# UBW32_MX460_v262.net
KiCad netlist of a schematic drawn in EAGLE
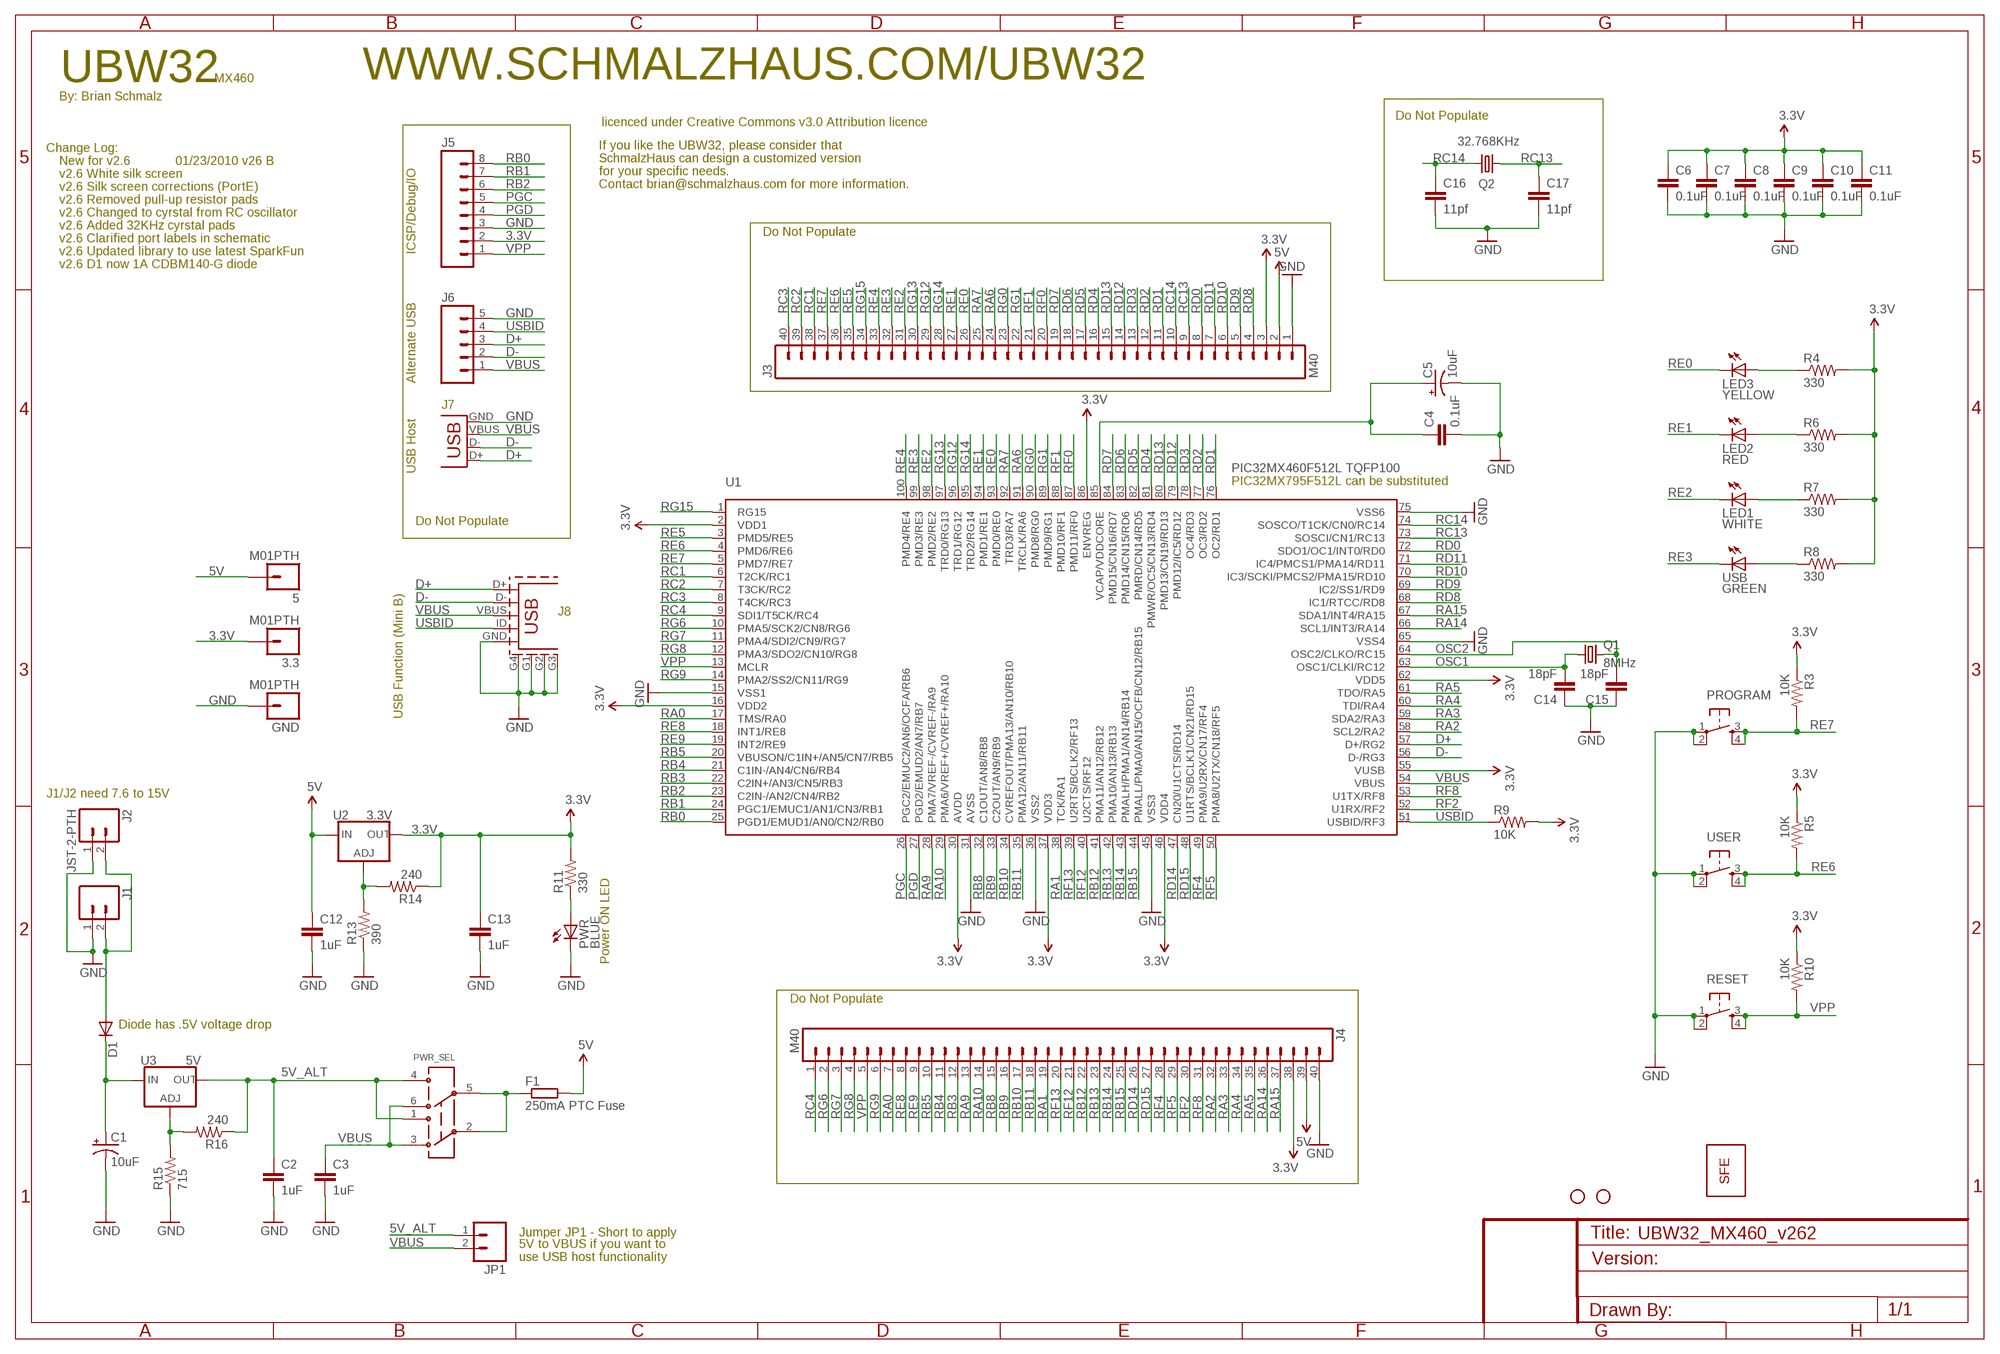
[diagram p0: schematic, sheet 1]

(export (version "E")
  (design (tool "Eeschema 10.0.6"))
  (components
    (comp (ref "3.3")
      (value "M01PTH")
      (footprint "eagle-import:1X01")
      (libsource (lib "eagle-import") (part "M01PTH"))
    )
    (comp (ref "5")
      (value "M01PTH")
      (footprint "eagle-import:1X01")
      (libsource (lib "eagle-import") (part "M01PTH"))
    )
    (comp (ref "C1")
      (value "10uF")
      (footprint "eagle-import:EIA3528")
      (libsource (lib "eagle-import") (part "CAP_POL3528"))
    )
    (comp (ref "C2")
      (value "1uF")
      (footprint "eagle-import:0402-CAP")
      (libsource (lib "eagle-import") (part "CAP0402-CAP"))
    )
    (comp (ref "C3")
      (value "1uF")
      (footprint "eagle-import:0402-CAP")
      (libsource (lib "eagle-import") (part "CAP0402-CAP"))
    )
    (comp (ref "C4")
      (value "0.1uF")
      (footprint "eagle-import:0402-CAP")
      (libsource (lib "eagle-import") (part "CAP0402-CAP"))
    )
    (comp (ref "C5")
      (value "10uF")
      (footprint "eagle-import:EIA3528")
      (libsource (lib "eagle-import") (part "CAP_POL3528"))
    )
    (comp (ref "C6")
      (value "0.1uF")
      (footprint "eagle-import:0402-CAP")
      (libsource (lib "eagle-import") (part "CAP0402-CAP"))
    )
    (comp (ref "C7")
      (value "0.1uF")
      (footprint "eagle-import:0402-CAP")
      (libsource (lib "eagle-import") (part "CAP0402-CAP"))
    )
    (comp (ref "C8")
      (value "0.1uF")
      (footprint "eagle-import:0402-CAP")
      (libsource (lib "eagle-import") (part "CAP0402-CAP"))
    )
    (comp (ref "C9")
      (value "0.1uF")
      (footprint "eagle-import:0402-CAP")
      (libsource (lib "eagle-import") (part "CAP0402-CAP"))
    )
    (comp (ref "C10")
      (value "0.1uF")
      (footprint "eagle-import:C0402")
      (libsource (lib "eagle-import") (part "CAP0402"))
    )
    (comp (ref "C11")
      (value "0.1uF")
      (footprint "eagle-import:0402-CAP")
      (libsource (lib "eagle-import") (part "CAP0402-CAP"))
    )
    (comp (ref "C12")
      (value "1uF")
      (footprint "eagle-import:C0402")
      (libsource (lib "eagle-import") (part "CAP0402"))
    )
    (comp (ref "C13")
      (value "1uF")
      (footprint "eagle-import:C0402")
      (libsource (lib "eagle-import") (part "CAP0402"))
    )
    (comp (ref "C14")
      (value "18pF")
      (footprint "eagle-import:0402-CAP")
      (libsource (lib "eagle-import") (part "CAP0402-CAP"))
    )
    (comp (ref "C15")
      (value "18pF")
      (footprint "eagle-import:0402-CAP")
      (libsource (lib "eagle-import") (part "CAP0402-CAP"))
    )
    (comp (ref "C16")
      (value "11pf")
      (footprint "eagle-import:0402-CAP")
      (libsource (lib "eagle-import") (part "CAP0402-CAP"))
    )
    (comp (ref "C17")
      (value "11pf")
      (footprint "eagle-import:0402-CAP")
      (libsource (lib "eagle-import") (part "CAP0402-CAP"))
    )
    (comp (ref "D1")
      (value "DIODESMA")
      (footprint "eagle-import:SMA-DIODE")
      (libsource (lib "eagle-import") (part "DIODESMA"))
    )
    (comp (ref "F1")
      (value "250mA PTC Fuse")
      (footprint "eagle-import:R1206")
      (libsource (lib "eagle-import") (part "R-EU_R1206"))
    )
    (comp (ref "GND")
      (value "M01PTH")
      (footprint "eagle-import:1X01")
      (libsource (lib "eagle-import") (part "M01PTH"))
    )
    (comp (ref "J1")
      (value "M02PTH")
      (footprint "eagle-import:1X02")
      (libsource (lib "eagle-import") (part "SparkFun-12-01-09_M02PTH"))
    )
    (comp (ref "J2")
      (value "JST-2-PTH")
      (footprint "eagle-import:S2B-PH")
      (libsource (lib "eagle-import") (part "M02-JST-2MM-SMT"))
    )
    (comp (ref "J3")
      (value "M40")
      (footprint "eagle-import:1X40")
      (libsource (lib "eagle-import") (part "M40"))
    )
    (comp (ref "J4")
      (value "M40")
      (footprint "eagle-import:1X40")
      (libsource (lib "eagle-import") (part "M40"))
    )
    (comp (ref "J5")
      (value "M08")
      (footprint "eagle-import:1X08")
      (libsource (lib "eagle-import") (part "M08"))
    )
    (comp (ref "J6")
      (value "M05PTH")
      (footprint "eagle-import:1X05")
      (libsource (lib "eagle-import") (part "M05PTH"))
    )
    (comp (ref "J7")
      (value "USB-A-S")
      (footprint "eagle-import:USB-A-S")
      (libsource (lib "eagle-import") (part "USB-A-S"))
    )
    (comp (ref "J8")
      (value "USB-MINIB")
      (footprint "eagle-import:USB-MINIB")
      (libsource (lib "eagle-import") (part "USB_5PIN"))
    )
    (comp (ref "JP1")
      (value "M02PTH")
      (footprint "eagle-import:1X02")
      (libsource (lib "eagle-import") (part "SparkFun-12-01-09_M02PTH"))
    )
    (comp (ref "LED1")
      (value "WHITE")
      (footprint "eagle-import:LED-0603")
      (libsource (lib "eagle-import") (part "LED0603"))
    )
    (comp (ref "LED2")
      (value "RED")
      (footprint "eagle-import:LED-0603")
      (libsource (lib "eagle-import") (part "LED0603"))
    )
    (comp (ref "LED3")
      (value "YELLOW")
      (footprint "eagle-import:LED-0603")
      (libsource (lib "eagle-import") (part "LED0603"))
    )
    (comp (ref "PROGRAM")
      (value "TAC_SWITCHSND")
      (footprint "eagle-import:TACTILE_SWITCH_SMD")
      (libsource (lib "eagle-import") (part "TAC_SWITCHSND"))
    )
    (comp (ref "PWR")
      (value "BLUE")
      (footprint "eagle-import:LED-0603")
      (libsource (lib "eagle-import") (part "LED0603"))
    )
    (comp (ref "PWR_SEL")
      (value "AYZ0202")
      (footprint "eagle-import:AYZ0202")
      (libsource (lib "eagle-import") (part "AYZ0202"))
    )
    (comp (ref "Q1")
      (value "8MHz")
      (footprint "eagle-import:CRYSTAL-SMD-5X3")
      (libsource (lib "eagle-import") (part "SparkFun11_03_09_CRYSTAL5X3"))
    )
    (comp (ref "Q2")
      (value "32.768KHz")
      (footprint "eagle-import:CRYSTAL-32KHZ-SMD")
      (libsource (lib "eagle-import") (part "CRYSTAL32-SMD"))
    )
    (comp (ref "R3")
      (value "10K")
      (footprint "eagle-import:0402-RES")
      (libsource (lib "eagle-import") (part "RESISTOR0402-RES"))
    )
    (comp (ref "R4")
      (value "330")
      (footprint "eagle-import:0402-RES")
      (libsource (lib "eagle-import") (part "RESISTOR0402-RES"))
    )
    (comp (ref "R5")
      (value "10K")
      (footprint "eagle-import:0402-RES")
      (libsource (lib "eagle-import") (part "RESISTOR0402-RES"))
    )
    (comp (ref "R6")
      (value "330")
      (footprint "eagle-import:0402-RES")
      (libsource (lib "eagle-import") (part "RESISTOR0402-RES"))
    )
    (comp (ref "R7")
      (value "330")
      (footprint "eagle-import:0402-RES")
      (libsource (lib "eagle-import") (part "RESISTOR0402-RES"))
    )
    (comp (ref "R8")
      (value "330")
      (footprint "eagle-import:0402-RES")
      (libsource (lib "eagle-import") (part "RESISTOR0402-RES"))
    )
    (comp (ref "R9")
      (value "10K")
      (footprint "eagle-import:0402-RES")
      (libsource (lib "eagle-import") (part "RESISTOR0402-RES"))
    )
    (comp (ref "R10")
      (value "10K")
      (footprint "eagle-import:0402-RES")
      (libsource (lib "eagle-import") (part "RESISTOR0402-RES"))
    )
    (comp (ref "R11")
      (value "330")
      (footprint "eagle-import:0402-RES")
      (libsource (lib "eagle-import") (part "RESISTOR0402-RES"))
    )
    (comp (ref "R13")
      (value "390")
      (footprint "eagle-import:0402-RES")
      (libsource (lib "eagle-import") (part "RESISTOR0402-RES"))
    )
    (comp (ref "R14")
      (value "240")
      (footprint "eagle-import:0402-RES")
      (libsource (lib "eagle-import") (part "RESISTOR0402-RES"))
    )
    (comp (ref "R15")
      (value "715")
      (footprint "eagle-import:0402-RES")
      (libsource (lib "eagle-import") (part "RESISTOR0402-RES"))
    )
    (comp (ref "R16")
      (value "240")
      (footprint "eagle-import:0402-RES")
      (libsource (lib "eagle-import") (part "RESISTOR0402-RES"))
    )
    (comp (ref "RESET")
      (value "TAC_SWITCHSND")
      (footprint "eagle-import:TACTILE_SWITCH_SMD")
      (libsource (lib "eagle-import") (part "TAC_SWITCHSND"))
    )
    (comp (ref "U$4")
      (value "LOGO-SFENEW")
      (footprint "eagle-import:SFE-NEW-WEBLOGO")
      (libsource (lib "eagle-import") (part "LOGO-SFENEW"))
    )
    (comp (ref "U$6")
      (value "STAND-OFF")
      (footprint "eagle-import:STAND-OFF")
      (libsource (lib "eagle-import") (part "STAND-OFF"))
    )
    (comp (ref "U$7")
      (value "STAND-OFF")
      (footprint "eagle-import:STAND-OFF")
      (libsource (lib "eagle-import") (part "STAND-OFF"))
    )
    (comp (ref "U1")
      (value "PIC32MX460F512L TQFP100")
      (footprint "eagle-import:TQFP100")
      (libsource (lib "eagle-import") (part "PIC32MX4XXLTQFP100"))
    )
    (comp (ref "U2")
      (value "3.3V")
      (footprint "eagle-import:SOT223")
      (libsource (lib "eagle-import") (part "V_REG_317SMD"))
    )
    (comp (ref "U3")
      (value "5V")
      (footprint "eagle-import:SOT223")
      (libsource (lib "eagle-import") (part "V_REG_317SMD"))
    )
    (comp (ref "USB")
      (value "GREEN")
      (footprint "eagle-import:LED-0603")
      (libsource (lib "eagle-import") (part "LED0603"))
    )
    (comp (ref "USER")
      (value "TAC_SWITCHSND")
      (footprint "eagle-import:TACTILE_SWITCH_SMD")
      (libsource (lib "eagle-import") (part "TAC_SWITCHSND"))
    )
  )
  (nets
    (net (code "1") (name "/5V_ALT") (class "Default")
      (node (ref "C2") (pin "1") (pinfunction "1_1") (pintype "passive"))
      (node (ref "JP1") (pin "1") (pinfunction "1_1") (pintype "passive"))
      (node (ref "PWR_SEL") (pin "1") (pinfunction "3_1") (pintype "bidirectional"))
      (node (ref "PWR_SEL") (pin "4") (pinfunction "6_4") (pintype "bidirectional"))
      (node (ref "R16") (pin "1") (pinfunction "1_1") (pintype "passive"))
      (node (ref "U3") (pin "2") (pinfunction "OUT_2") (pintype "output"))
    )
    (net (code "2") (name "/D+") (class "Default")
      (node (ref "J6") (pin "3") (pinfunction "3_3") (pintype "passive"))
      (node (ref "J7") (pin "D+") (pinfunction "D+_D+") (pintype "bidirectional"))
      (node (ref "J8") (pin "D+") (pinfunction "D+_D+") (pintype "bidirectional"))
      (node (ref "U1") (pin "57") (pinfunction "D+/RG2_57") (pintype "bidirectional"))
    )
    (net (code "3") (name "/D-") (class "Default")
      (node (ref "J6") (pin "2") (pinfunction "2_2") (pintype "passive"))
      (node (ref "J7") (pin "D-") (pinfunction "D-_D-") (pintype "bidirectional"))
      (node (ref "J8") (pin "D-") (pinfunction "D-_D-") (pintype "bidirectional"))
      (node (ref "U1") (pin "56") (pinfunction "D-/RG3_56") (pintype "bidirectional"))
    )
    (net (code "4") (name "/OSC1") (class "Default")
      (node (ref "C14") (pin "2") (pinfunction "2_2") (pintype "passive"))
      (node (ref "Q1") (pin "1") (pinfunction "1_1") (pintype "passive"))
      (node (ref "U1") (pin "63") (pinfunction "OSC1/CLKI/RC12_63") (pintype "bidirectional"))
    )
    (net (code "5") (name "/OSC2") (class "Default")
      (node (ref "C15") (pin "2") (pinfunction "2_2") (pintype "passive"))
      (node (ref "Q1") (pin "3") (pinfunction "2_3") (pintype "passive"))
      (node (ref "U1") (pin "64") (pinfunction "OSC2/CLKO/RC15_64") (pintype "bidirectional"))
    )
    (net (code "6") (name "/PGC") (class "Default")
      (node (ref "J5") (pin "5") (pinfunction "5_5") (pintype "passive"))
      (node (ref "U1") (pin "26") (pinfunction "PGC2/EMUC2/AN6/OCFA/RB6_26") (pintype "bidirectional"))
    )
    (net (code "7") (name "/PGD") (class "Default")
      (node (ref "J5") (pin "4") (pinfunction "4_4") (pintype "passive"))
      (node (ref "U1") (pin "27") (pinfunction "PGD2/EMUD2/AN7/RB7_27") (pintype "bidirectional"))
    )
    (net (code "8") (name "/RA0") (class "Default")
      (node (ref "J4") (pin "7") (pinfunction "7_7") (pintype "passive"))
      (node (ref "U1") (pin "17") (pinfunction "TMS/RA0_17") (pintype "bidirectional"))
    )
    (net (code "9") (name "/RA1") (class "Default")
      (node (ref "J4") (pin "19") (pinfunction "19_19") (pintype "passive"))
      (node (ref "U1") (pin "38") (pinfunction "TCK/RA1_38") (pintype "bidirectional"))
    )
    (net (code "10") (name "/RA2") (class "Default")
      (node (ref "J4") (pin "32") (pinfunction "32_32") (pintype "passive"))
      (node (ref "U1") (pin "58") (pinfunction "SCL2/RA2_58") (pintype "bidirectional"))
    )
    (net (code "11") (name "/RA3") (class "Default")
      (node (ref "J4") (pin "33") (pinfunction "33_33") (pintype "passive"))
      (node (ref "U1") (pin "59") (pinfunction "SDA2/RA3_59") (pintype "bidirectional"))
    )
    (net (code "12") (name "/RA4") (class "Default")
      (node (ref "J4") (pin "34") (pinfunction "34_34") (pintype "passive"))
      (node (ref "U1") (pin "60") (pinfunction "TDI/RA4_60") (pintype "bidirectional"))
    )
    (net (code "13") (name "/RA5") (class "Default")
      (node (ref "J4") (pin "35") (pinfunction "35_35") (pintype "passive"))
      (node (ref "U1") (pin "61") (pinfunction "TDO/RA5_61") (pintype "bidirectional"))
    )
    (net (code "14") (name "/RA6") (class "Default")
      (node (ref "J3") (pin "24") (pinfunction "24_24") (pintype "passive"))
      (node (ref "U1") (pin "91") (pinfunction "TRCLK/RA6_91") (pintype "bidirectional"))
    )
    (net (code "15") (name "/RA7") (class "Default")
      (node (ref "J3") (pin "25") (pinfunction "25_25") (pintype "passive"))
      (node (ref "U1") (pin "92") (pinfunction "TRD3/RA7_92") (pintype "bidirectional"))
    )
    (net (code "16") (name "/RA9") (class "Default")
      (node (ref "J4") (pin "13") (pinfunction "13_13") (pintype "passive"))
      (node (ref "U1") (pin "28") (pinfunction "PMA7/VREF-/CVREF-/RA9_28") (pintype "bidirectional"))
    )
    (net (code "17") (name "/RA10") (class "Default")
      (node (ref "J4") (pin "14") (pinfunction "14_14") (pintype "passive"))
      (node (ref "U1") (pin "29") (pinfunction "PMA6/VREF+/CVREF+/RA10_29") (pintype "bidirectional"))
    )
    (net (code "18") (name "/RA14") (class "Default")
      (node (ref "J4") (pin "36") (pinfunction "36_36") (pintype "passive"))
      (node (ref "U1") (pin "66") (pinfunction "SCL1/INT3/RA14_66") (pintype "bidirectional"))
    )
    (net (code "19") (name "/RA15") (class "Default")
      (node (ref "J4") (pin "37") (pinfunction "37_37") (pintype "passive"))
      (node (ref "U1") (pin "67") (pinfunction "SDA1/INT4/RA15_67") (pintype "bidirectional"))
    )
    (net (code "20") (name "/RB0") (class "Default")
      (node (ref "J5") (pin "8") (pinfunction "8_8") (pintype "passive"))
      (node (ref "U1") (pin "25") (pinfunction "PGD1/EMUD1/AN0/CN2/RB0_25") (pintype "bidirectional"))
    )
    (net (code "21") (name "/RB1") (class "Default")
      (node (ref "J5") (pin "7") (pinfunction "7_7") (pintype "passive"))
      (node (ref "U1") (pin "24") (pinfunction "PGC1/EMUC1/AN1/CN3/RB1_24") (pintype "bidirectional"))
    )
    (net (code "22") (name "/RB2") (class "Default")
      (node (ref "J5") (pin "6") (pinfunction "6_6") (pintype "passive"))
      (node (ref "U1") (pin "23") (pinfunction "C2IN-/AN2/CN4/RB2_23") (pintype "bidirectional"))
    )
    (net (code "23") (name "/RB3") (class "Default")
      (node (ref "J4") (pin "12") (pinfunction "12_12") (pintype "passive"))
      (node (ref "U1") (pin "22") (pinfunction "C2IN+/AN3/CN5/RB3_22") (pintype "bidirectional"))
    )
    (net (code "24") (name "/RB4") (class "Default")
      (node (ref "J4") (pin "11") (pinfunction "11_11") (pintype "passive"))
      (node (ref "U1") (pin "21") (pinfunction "C1IN-/AN4/CN6/RB4_21") (pintype "bidirectional"))
    )
    (net (code "25") (name "/RB5") (class "Default")
      (node (ref "J4") (pin "10") (pinfunction "10_10") (pintype "passive"))
      (node (ref "U1") (pin "20") (pinfunction "VBUSON/C1IN+/AN5/CN7/RB5_20") (pintype "bidirectional"))
    )
    (net (code "26") (name "/RB8") (class "Default")
      (node (ref "J4") (pin "15") (pinfunction "15_15") (pintype "passive"))
      (node (ref "U1") (pin "32") (pinfunction "C1OUT/AN8/RB8_32") (pintype "bidirectional"))
    )
    (net (code "27") (name "/RB9") (class "Default")
      (node (ref "J4") (pin "16") (pinfunction "16_16") (pintype "passive"))
      (node (ref "U1") (pin "33") (pinfunction "C2OUT/AN9/RB9_33") (pintype "bidirectional"))
    )
    (net (code "28") (name "/RB10") (class "Default")
      (node (ref "J4") (pin "17") (pinfunction "17_17") (pintype "passive"))
      (node (ref "U1") (pin "34") (pinfunction "CVREFOUT/PMA13/AN10/RB10_34") (pintype "bidirectional"))
    )
    (net (code "29") (name "/RB11") (class "Default")
      (node (ref "J4") (pin "18") (pinfunction "18_18") (pintype "passive"))
      (node (ref "U1") (pin "35") (pinfunction "PMA12/AN11/RB11_35") (pintype "bidirectional"))
    )
    (net (code "30") (name "/RB12") (class "Default")
      (node (ref "J4") (pin "22") (pinfunction "22_22") (pintype "passive"))
      (node (ref "U1") (pin "41") (pinfunction "PMA11/AN12/RB12_41") (pintype "bidirectional"))
    )
    (net (code "31") (name "/RB13") (class "Default")
      (node (ref "J4") (pin "23") (pinfunction "23_23") (pintype "passive"))
      (node (ref "U1") (pin "42") (pinfunction "PMA10/AN13/RB13_42") (pintype "bidirectional"))
    )
    (net (code "32") (name "/RB14") (class "Default")
      (node (ref "J4") (pin "24") (pinfunction "24_24") (pintype "passive"))
      (node (ref "U1") (pin "43") (pinfunction "PMALH/PMA1/AN14/RB14_43") (pintype "bidirectional"))
    )
    (net (code "33") (name "/RB15") (class "Default")
      (node (ref "J4") (pin "25") (pinfunction "25_25") (pintype "passive"))
      (node (ref "U1") (pin "44") (pinfunction "PMALL/PMA0/AN15/OCFB/CN12/RB15_44") (pintype "bidirectional"))
    )
    (net (code "34") (name "/RC1") (class "Default")
      (node (ref "J3") (pin "38") (pinfunction "38_38") (pintype "passive"))
      (node (ref "U1") (pin "6") (pinfunction "T2CK/RC1_6") (pintype "bidirectional"))
    )
    (net (code "35") (name "/RC2") (class "Default")
      (node (ref "J3") (pin "39") (pinfunction "39_39") (pintype "passive"))
      (node (ref "U1") (pin "7") (pinfunction "T3CK/RC2_7") (pintype "bidirectional"))
    )
    (net (code "36") (name "/RC3") (class "Default")
      (node (ref "J3") (pin "40") (pinfunction "40_40") (pintype "passive"))
      (node (ref "U1") (pin "8") (pinfunction "T4CK/RC3_8") (pintype "bidirectional"))
    )
    (net (code "37") (name "/RC4") (class "Default")
      (node (ref "J4") (pin "1") (pinfunction "1_1") (pintype "passive"))
      (node (ref "U1") (pin "9") (pinfunction "SDI1/T5CK/RC4_9") (pintype "bidirectional"))
    )
    (net (code "38") (name "/RC13") (class "Default")
      (node (ref "C17") (pin "1") (pinfunction "1_1") (pintype "passive"))
      (node (ref "J3") (pin "9") (pinfunction "9_9") (pintype "passive"))
      (node (ref "Q2") (pin "X1") (pinfunction "1_X1") (pintype "passive"))
      (node (ref "U1") (pin "73") (pinfunction "SOSCI/CN1/RC13_73") (pintype "bidirectional"))
    )
    (net (code "39") (name "/RC14") (class "Default")
      (node (ref "C16") (pin "1") (pinfunction "1_1") (pintype "passive"))
      (node (ref "J3") (pin "10") (pinfunction "10_10") (pintype "passive"))
      (node (ref "Q2") (pin "X2") (pinfunction "2_X2") (pintype "passive"))
      (node (ref "U1") (pin "74") (pinfunction "SOSCO/T1CK/CN0/RC14_74") (pintype "bidirectional"))
    )
    (net (code "40") (name "/RD0") (class "Default")
      (node (ref "J3") (pin "8") (pinfunction "8_8") (pintype "passive"))
      (node (ref "U1") (pin "72") (pinfunction "SDO1/OC1/INT0/RD0_72") (pintype "bidirectional"))
    )
    (net (code "41") (name "/RD1") (class "Default")
      (node (ref "J3") (pin "11") (pinfunction "11_11") (pintype "passive"))
      (node (ref "U1") (pin "76") (pinfunction "OC2/RD1_76") (pintype "bidirectional"))
    )
    (net (code "42") (name "/RD2") (class "Default")
      (node (ref "J3") (pin "12") (pinfunction "12_12") (pintype "passive"))
      (node (ref "U1") (pin "77") (pinfunction "OC3/RD2_77") (pintype "bidirectional"))
    )
    (net (code "43") (name "/RD3") (class "Default")
      (node (ref "J3") (pin "13") (pinfunction "13_13") (pintype "passive"))
      (node (ref "U1") (pin "78") (pinfunction "OC4/RD3_78") (pintype "bidirectional"))
    )
    (net (code "44") (name "/RD4") (class "Default")
      (node (ref "J3") (pin "16") (pinfunction "16_16") (pintype "passive"))
      (node (ref "U1") (pin "81") (pinfunction "PMWR/OC5/CN13/RD4_81") (pintype "bidirectional"))
    )
    (net (code "45") (name "/RD5") (class "Default")
      (node (ref "J3") (pin "17") (pinfunction "17_17") (pintype "passive"))
      (node (ref "U1") (pin "82") (pinfunction "PMRD/CN14/RD5_82") (pintype "bidirectional"))
    )
    (net (code "46") (name "/RD6") (class "Default")
      (node (ref "J3") (pin "18") (pinfunction "18_18") (pintype "passive"))
      (node (ref "U1") (pin "83") (pinfunction "PMD14/CN15/RD6_83") (pintype "bidirectional"))
    )
    (net (code "47") (name "/RD7") (class "Default")
      (node (ref "J3") (pin "19") (pinfunction "19_19") (pintype "passive"))
      (node (ref "U1") (pin "84") (pinfunction "PMD15/CN16/RD7_84") (pintype "bidirectional"))
    )
    (net (code "48") (name "/RD8") (class "Default")
      (node (ref "J3") (pin "4") (pinfunction "4_4") (pintype "passive"))
      (node (ref "U1") (pin "68") (pinfunction "IC1/RTCC/RD8_68") (pintype "bidirectional"))
    )
    (net (code "49") (name "/RD9") (class "Default")
      (node (ref "J3") (pin "5") (pinfunction "5_5") (pintype "passive"))
      (node (ref "U1") (pin "69") (pinfunction "IC2/SS1/RD9_69") (pintype "bidirectional"))
    )
    (net (code "50") (name "/RD10") (class "Default")
      (node (ref "J3") (pin "6") (pinfunction "6_6") (pintype "passive"))
      (node (ref "U1") (pin "70") (pinfunction "IC3/SCKI/PMCS2/PMA15/RD10_70") (pintype "bidirectional"))
    )
    (net (code "51") (name "/RD11") (class "Default")
      (node (ref "J3") (pin "7") (pinfunction "7_7") (pintype "passive"))
      (node (ref "U1") (pin "71") (pinfunction "IC4/PMCS1/PMA14/RD11_71") (pintype "bidirectional"))
    )
    (net (code "52") (name "/RD12") (class "Default")
      (node (ref "J3") (pin "14") (pinfunction "14_14") (pintype "passive"))
      (node (ref "U1") (pin "79") (pinfunction "PMD12/IC5/RD12_79") (pintype "bidirectional"))
    )
    (net (code "53") (name "/RD13") (class "Default")
      (node (ref "J3") (pin "15") (pinfunction "15_15") (pintype "passive"))
      (node (ref "U1") (pin "80") (pinfunction "PMD13/CN19/RD13_80") (pintype "bidirectional"))
    )
    (net (code "54") (name "/RD14") (class "Default")
      (node (ref "J4") (pin "26") (pinfunction "26_26") (pintype "passive"))
      (node (ref "U1") (pin "47") (pinfunction "CN20/U1CTS/RD14_47") (pintype "bidirectional"))
    )
    (net (code "55") (name "/RD15") (class "Default")
      (node (ref "J4") (pin "27") (pinfunction "27_27") (pintype "passive"))
      (node (ref "U1") (pin "48") (pinfunction "U1RTS/BCLK1/CN21/RD15_48") (pintype "bidirectional"))
    )
    (net (code "56") (name "/RE0") (class "Default")
      (node (ref "J3") (pin "26") (pinfunction "26_26") (pintype "passive"))
      (node (ref "LED3") (pin "C") (pinfunction "C_C") (pintype "passive"))
      (node (ref "U1") (pin "93") (pinfunction "PMD0/RE0_93") (pintype "bidirectional"))
    )
    (net (code "57") (name "/RE1") (class "Default")
      (node (ref "J3") (pin "27") (pinfunction "27_27") (pintype "passive"))
      (node (ref "LED2") (pin "C") (pinfunction "C_C") (pintype "passive"))
      (node (ref "U1") (pin "94") (pinfunction "PMD1/RE1_94") (pintype "bidirectional"))
    )
    (net (code "58") (name "/RE2") (class "Default")
      (node (ref "J3") (pin "31") (pinfunction "31_31") (pintype "passive"))
      (node (ref "LED1") (pin "C") (pinfunction "C_C") (pintype "passive"))
      (node (ref "U1") (pin "98") (pinfunction "PMD2/RE2_98") (pintype "bidirectional"))
    )
    (net (code "59") (name "/RE3") (class "Default")
      (node (ref "J3") (pin "32") (pinfunction "32_32") (pintype "passive"))
      (node (ref "U1") (pin "99") (pinfunction "PMD3/RE3_99") (pintype "bidirectional"))
      (node (ref "USB") (pin "C") (pinfunction "C_C") (pintype "passive"))
    )
    (net (code "60") (name "/RE4") (class "Default")
      (node (ref "J3") (pin "33") (pinfunction "33_33") (pintype "passive"))
      (node (ref "U1") (pin "100") (pinfunction "PMD4/RE4_100") (pintype "bidirectional"))
    )
    (net (code "61") (name "/RE5") (class "Default")
      (node (ref "J3") (pin "35") (pinfunction "35_35") (pintype "passive"))
      (node (ref "U1") (pin "3") (pinfunction "PMD5/RE5_3") (pintype "bidirectional"))
    )
    (net (code "62") (name "/RE6") (class "Default")
      (node (ref "J3") (pin "36") (pinfunction "36_36") (pintype "passive"))
      (node (ref "R5") (pin "2") (pinfunction "2_2") (pintype "passive"))
      (node (ref "U1") (pin "4") (pinfunction "PMD6/RE6_4") (pintype "bidirectional"))
      (node (ref "USER") (pin "3") (pinfunction "3_3") (pintype "passive"))
      (node (ref "USER") (pin "4") (pinfunction "4_4") (pintype "passive"))
    )
    (net (code "63") (name "/RE7") (class "Default")
      (node (ref "J3") (pin "37") (pinfunction "37_37") (pintype "passive"))
      (node (ref "PROGRAM") (pin "3") (pinfunction "3_3") (pintype "passive"))
      (node (ref "PROGRAM") (pin "4") (pinfunction "4_4") (pintype "passive"))
      (node (ref "R3") (pin "2") (pinfunction "2_2") (pintype "passive"))
      (node (ref "U1") (pin "5") (pinfunction "PMD7/RE7_5") (pintype "bidirectional"))
    )
    (net (code "64") (name "/RE8") (class "Default")
      (node (ref "J4") (pin "8") (pinfunction "8_8") (pintype "passive"))
      (node (ref "U1") (pin "18") (pinfunction "INT1/RE8_18") (pintype "bidirectional"))
    )
    (net (code "65") (name "/RE9") (class "Default")
      (node (ref "J4") (pin "9") (pinfunction "9_9") (pintype "passive"))
      (node (ref "U1") (pin "19") (pinfunction "INT2/RE9_19") (pintype "bidirectional"))
    )
    (net (code "66") (name "/RF0") (class "Default")
      (node (ref "J3") (pin "20") (pinfunction "20_20") (pintype "passive"))
      (node (ref "U1") (pin "87") (pinfunction "PMD11/RF0_87") (pintype "bidirectional"))
    )
    (net (code "67") (name "/RF1") (class "Default")
      (node (ref "J3") (pin "21") (pinfunction "21_21") (pintype "passive"))
      (node (ref "U1") (pin "88") (pinfunction "PMD10/RF1_88") (pintype "bidirectional"))
    )
    (net (code "68") (name "/RF2") (class "Default")
      (node (ref "J4") (pin "30") (pinfunction "30_30") (pintype "passive"))
      (node (ref "U1") (pin "52") (pinfunction "U1RX/RF2_52") (pintype "bidirectional"))
    )
    (net (code "69") (name "/RF4") (class "Default")
      (node (ref "J4") (pin "28") (pinfunction "28_28") (pintype "passive"))
      (node (ref "U1") (pin "49") (pinfunction "PMA9/U2RX/CN17/RF4_49") (pintype "bidirectional"))
    )
    (net (code "70") (name "/RF5") (class "Default")
      (node (ref "J4") (pin "29") (pinfunction "29_29") (pintype "passive"))
      (node (ref "U1") (pin "50") (pinfunction "PMA8/U2TX/CN18/RF5_50") (pintype "bidirectional"))
    )
    (net (code "71") (name "/RF8") (class "Default")
      (node (ref "J4") (pin "31") (pinfunction "31_31") (pintype "passive"))
      (node (ref "U1") (pin "53") (pinfunction "U1TX/RF8_53") (pintype "bidirectional"))
    )
    (net (code "72") (name "/RF12") (class "Default")
      (node (ref "J4") (pin "21") (pinfunction "21_21") (pintype "passive"))
      (node (ref "U1") (pin "40") (pinfunction "U2CTS/RF12_40") (pintype "bidirectional"))
    )
    (net (code "73") (name "/RF13") (class "Default")
      (node (ref "J4") (pin "20") (pinfunction "20_20") (pintype "passive"))
      (node (ref "U1") (pin "39") (pinfunction "U2RTS/BCLK2/RF13_39") (pintype "bidirectional"))
    )
    (net (code "74") (name "/RG0") (class "Default")
      (node (ref "J3") (pin "23") (pinfunction "23_23") (pintype "passive"))
      (node (ref "U1") (pin "90") (pinfunction "PMD8/RG0_90") (pintype "bidirectional"))
    )
    (net (code "75") (name "/RG1") (class "Default")
      (node (ref "J3") (pin "22") (pinfunction "22_22") (pintype "passive"))
      (node (ref "U1") (pin "89") (pinfunction "PMD9/RG1_89") (pintype "bidirectional"))
    )
    (net (code "76") (name "/RG6") (class "Default")
      (node (ref "J4") (pin "2") (pinfunction "2_2") (pintype "passive"))
      (node (ref "U1") (pin "10") (pinfunction "PMA5/SCK2/CN8/RG6_10") (pintype "bidirectional"))
    )
    (net (code "77") (name "/RG7") (class "Default")
      (node (ref "J4") (pin "3") (pinfunction "3_3") (pintype "passive"))
      (node (ref "U1") (pin "11") (pinfunction "PMA4/SDI2/CN9/RG7_11") (pintype "bidirectional"))
    )
    (net (code "78") (name "/RG8") (class "Default")
      (node (ref "J4") (pin "4") (pinfunction "4_4") (pintype "passive"))
      (node (ref "U1") (pin "12") (pinfunction "PMA3/SDO2/CN10/RG8_12") (pintype "bidirectional"))
    )
    (net (code "79") (name "/RG9") (class "Default")
      (node (ref "J4") (pin "6") (pinfunction "6_6") (pintype "passive"))
      (node (ref "U1") (pin "14") (pinfunction "PMA2/SS2/CN11/RG9_14") (pintype "bidirectional"))
    )
    (net (code "80") (name "/RG12") (class "Default")
      (node (ref "J3") (pin "29") (pinfunction "29_29") (pintype "passive"))
      (node (ref "U1") (pin "96") (pinfunction "TRD1/RG12_96") (pintype "bidirectional"))
    )
    (net (code "81") (name "/RG13") (class "Default")
      (node (ref "J3") (pin "30") (pinfunction "30_30") (pintype "passive"))
      (node (ref "U1") (pin "97") (pinfunction "TRD0/RG13_97") (pintype "bidirectional"))
    )
    (net (code "82") (name "/RG14") (class "Default")
      (node (ref "J3") (pin "28") (pinfunction "28_28") (pintype "passive"))
      (node (ref "U1") (pin "95") (pinfunction "TRD2/RG14_95") (pintype "bidirectional"))
    )
    (net (code "83") (name "/RG15") (class "Default")
      (node (ref "J3") (pin "34") (pinfunction "34_34") (pintype "passive"))
      (node (ref "U1") (pin "1") (pinfunction "RG15_1") (pintype "bidirectional"))
    )
    (net (code "84") (name "/USBID") (class "Default")
      (node (ref "J6") (pin "4") (pinfunction "4_4") (pintype "passive"))
      (node (ref "J8") (pin "ID") (pinfunction "USB_ID_ID") (pintype "bidirectional"))
      (node (ref "R9") (pin "1") (pinfunction "1_1") (pintype "passive"))
      (node (ref "U1") (pin "51") (pinfunction "USBID/RF3_51") (pintype "bidirectional"))
    )
    (net (code "85") (name "/VBUS") (class "Default")
      (node (ref "C3") (pin "1") (pinfunction "1_1") (pintype "passive"))
      (node (ref "J6") (pin "1") (pinfunction "1_1") (pintype "passive"))
      (node (ref "J7") (pin "VBUS") (pinfunction "VBUS_VBUS") (pintype "bidirectional"))
      (node (ref "J8") (pin "VBUS") (pinfunction "VBUS_VBUS") (pintype "bidirectional"))
      (node (ref "JP1") (pin "2") (pinfunction "2_2") (pintype "passive"))
      (node (ref "PWR_SEL") (pin "3") (pinfunction "1_3") (pintype "bidirectional"))
      (node (ref "PWR_SEL") (pin "6") (pinfunction "4_6") (pintype "bidirectional"))
      (node (ref "U1") (pin "54") (pinfunction "VBUS_54") (pintype "bidirectional"))
    )
    (net (code "86") (name "/VPP") (class "Default")
      (node (ref "J4") (pin "5") (pinfunction "5_5") (pintype "passive"))
      (node (ref "J5") (pin "1") (pinfunction "1_1") (pintype "passive"))
      (node (ref "R10") (pin "2") (pinfunction "2_2") (pintype "passive"))
      (node (ref "RESET") (pin "3") (pinfunction "3_3") (pintype "passive"))
      (node (ref "RESET") (pin "4") (pinfunction "4_4") (pintype "passive"))
      (node (ref "U1") (pin "13") (pinfunction "MCLR_13") (pintype "bidirectional"))
    )
    (net (code "87") (name "3.3V") (class "Default")
      (node (ref "3.3") (pin "1") (pinfunction "1_1") (pintype "passive"))
      (node (ref "C10") (pin "1") (pinfunction "1_1") (pintype "passive"))
      (node (ref "C11") (pin "1") (pinfunction "1_1") (pintype "passive"))
      (node (ref "C13") (pin "1") (pinfunction "1_1") (pintype "passive"))
      (node (ref "C6") (pin "1") (pinfunction "1_1") (pintype "passive"))
      (node (ref "C7") (pin "1") (pinfunction "1_1") (pintype "passive"))
      (node (ref "C8") (pin "1") (pinfunction "1_1") (pintype "passive"))
      (node (ref "C9") (pin "1") (pinfunction "1_1") (pintype "passive"))
      (node (ref "J3") (pin "3") (pinfunction "3_3") (pintype "passive"))
      (node (ref "J4") (pin "38") (pinfunction "38_38") (pintype "passive"))
      (node (ref "J5") (pin "2") (pinfunction "2_2") (pintype "passive"))
      (node (ref "R10") (pin "1") (pinfunction "1_1") (pintype "passive"))
      (node (ref "R11") (pin "2") (pinfunction "2_2") (pintype "passive"))
      (node (ref "R14") (pin "1") (pinfunction "1_1") (pintype "passive"))
      (node (ref "R3") (pin "1") (pinfunction "1_1") (pintype "passive"))
      (node (ref "R4") (pin "2") (pinfunction "2_2") (pintype "passive"))
      (node (ref "R5") (pin "1") (pinfunction "1_1") (pintype "passive"))
      (node (ref "R6") (pin "2") (pinfunction "2_2") (pintype "passive"))
      (node (ref "R7") (pin "2") (pinfunction "2_2") (pintype "passive"))
      (node (ref "R8") (pin "2") (pinfunction "2_2") (pintype "passive"))
      (node (ref "R9") (pin "2") (pinfunction "2_2") (pintype "passive"))
      (node (ref "U1") (pin "16") (pinfunction "VDD2_16") (pintype "bidirectional"))
      (node (ref "U1") (pin "2") (pinfunction "VDD1_2") (pintype "bidirectional"))
      (node (ref "U1") (pin "30") (pinfunction "AVDD_30") (pintype "bidirectional"))
      (node (ref "U1") (pin "37") (pinfunction "VDD3_37") (pintype "bidirectional"))
      (node (ref "U1") (pin "46") (pinfunction "VDD4_46") (pintype "bidirectional"))
      (node (ref "U1") (pin "55") (pinfunction "VUSB_55") (pintype "bidirectional"))
      (node (ref "U1") (pin "62") (pinfunction "VDD5_62") (pintype "bidirectional"))
      (node (ref "U1") (pin "86") (pinfunction "ENVREG_86") (pintype "bidirectional"))
      (node (ref "U2") (pin "2") (pinfunction "OUT_2") (pintype "output"))
    )
    (net (code "88") (name "5V") (class "Default")
      (node (ref "5") (pin "1") (pinfunction "1_1") (pintype "passive"))
      (node (ref "C12") (pin "1") (pinfunction "1_1") (pintype "passive"))
      (node (ref "F1") (pin "2") (pinfunction "2_2") (pintype "passive"))
      (node (ref "J3") (pin "2") (pinfunction "2_2") (pintype "passive"))
      (node (ref "J4") (pin "39") (pinfunction "39_39") (pintype "passive"))
      (node (ref "U2") (pin "3") (pinfunction "IN_3") (pintype "input"))
    )
    (net (code "89") (name "GND") (class "Default")
      (node (ref "C1") (pin "C") (pinfunction "-_C") (pintype "passive"))
      (node (ref "C10") (pin "2") (pinfunction "2_2") (pintype "passive"))
      (node (ref "C11") (pin "2") (pinfunction "2_2") (pintype "passive"))
      (node (ref "C12") (pin "2") (pinfunction "2_2") (pintype "passive"))
      (node (ref "C13") (pin "2") (pinfunction "2_2") (pintype "passive"))
      (node (ref "C14") (pin "1") (pinfunction "1_1") (pintype "passive"))
      (node (ref "C15") (pin "1") (pinfunction "1_1") (pintype "passive"))
      (node (ref "C16") (pin "2") (pinfunction "2_2") (pintype "passive"))
      (node (ref "C17") (pin "2") (pinfunction "2_2") (pintype "passive"))
      (node (ref "C2") (pin "2") (pinfunction "2_2") (pintype "passive"))
      (node (ref "C3") (pin "2") (pinfunction "2_2") (pintype "passive"))
      (node (ref "C4") (pin "2") (pinfunction "2_2") (pintype "passive"))
      (node (ref "C5") (pin "C") (pinfunction "-_C") (pintype "passive"))
      (node (ref "C6") (pin "2") (pinfunction "2_2") (pintype "passive"))
      (node (ref "C7") (pin "2") (pinfunction "2_2") (pintype "passive"))
      (node (ref "C8") (pin "2") (pinfunction "2_2") (pintype "passive"))
      (node (ref "C9") (pin "2") (pinfunction "2_2") (pintype "passive"))
      (node (ref "GND") (pin "1") (pinfunction "1_1") (pintype "passive"))
      (node (ref "J1") (pin "1") (pinfunction "1_1") (pintype "passive"))
      (node (ref "J2") (pin "1") (pinfunction "1_1") (pintype "passive"))
      (node (ref "J3") (pin "1") (pinfunction "1_1") (pintype "passive"))
      (node (ref "J4") (pin "40") (pinfunction "40_40") (pintype "passive"))
      (node (ref "J5") (pin "3") (pinfunction "3_3") (pintype "passive"))
      (node (ref "J6") (pin "5") (pinfunction "5_5") (pintype "passive"))
      (node (ref "J7") (pin "GND") (pinfunction "GND_GND") (pintype "bidirectional"))
      (node (ref "J8") (pin "G1") (pinfunction "P$1_G1") (pintype "bidirectional"))
      (node (ref "J8") (pin "G2") (pinfunction "P$2_G2") (pintype "bidirectional"))
      (node (ref "J8") (pin "G3") (pinfunction "P$3_G3") (pintype "bidirectional"))
      (node (ref "J8") (pin "G4") (pinfunction "SHIELD_G4") (pintype "bidirectional"))
      (node (ref "J8") (pin "GND") (pinfunction "GND_GND") (pintype "bidirectional"))
      (node (ref "PROGRAM") (pin "1") (pinfunction "1_1") (pintype "passive"))
      (node (ref "PROGRAM") (pin "2") (pinfunction "2_2") (pintype "passive"))
      (node (ref "PWR") (pin "C") (pinfunction "C_C") (pintype "passive"))
      (node (ref "R13") (pin "1") (pinfunction "1_1") (pintype "passive"))
      (node (ref "R15") (pin "1") (pinfunction "1_1") (pintype "passive"))
      (node (ref "RESET") (pin "1") (pinfunction "1_1") (pintype "passive"))
      (node (ref "RESET") (pin "2") (pinfunction "2_2") (pintype "passive"))
      (node (ref "U1") (pin "15") (pinfunction "VSS1_15") (pintype "bidirectional"))
      (node (ref "U1") (pin "31") (pinfunction "AVSS_31") (pintype "bidirectional"))
      (node (ref "U1") (pin "36") (pinfunction "VSS2_36") (pintype "bidirectional"))
      (node (ref "U1") (pin "45") (pinfunction "VSS3_45") (pintype "bidirectional"))
      (node (ref "U1") (pin "65") (pinfunction "VSS4_65") (pintype "bidirectional"))
      (node (ref "U1") (pin "75") (pinfunction "VSS6_75") (pintype "bidirectional"))
      (node (ref "USER") (pin "1") (pinfunction "1_1") (pintype "passive"))
      (node (ref "USER") (pin "2") (pinfunction "2_2") (pintype "passive"))
    )
    (net (code "90") (name "Net-(C1-+)") (class "Default")
      (node (ref "C1") (pin "A") (pinfunction "+_A") (pintype "passive"))
      (node (ref "D1") (pin "C") (pinfunction "C_C") (pintype "passive"))
      (node (ref "U3") (pin "3") (pinfunction "IN_3") (pintype "input"))
    )
    (net (code "91") (name "Net-(C5-+)") (class "Default")
      (node (ref "C4") (pin "1") (pinfunction "1_1") (pintype "passive"))
      (node (ref "C5") (pin "A") (pinfunction "+_A") (pintype "passive"))
      (node (ref "U1") (pin "85") (pinfunction "VCAP/VDDCORE_85") (pintype "bidirectional"))
    )
    (net (code "92") (name "Net-(D1-PadA)") (class "Default")
      (node (ref "D1") (pin "A") (pinfunction "A_A") (pintype "passive"))
      (node (ref "J1") (pin "2") (pinfunction "2_2") (pintype "passive"))
      (node (ref "J2") (pin "2") (pinfunction "2_2") (pintype "passive"))
    )
    (net (code "93") (name "Net-(F1-Pad1)") (class "Default")
      (node (ref "F1") (pin "1") (pinfunction "1_1") (pintype "passive"))
      (node (ref "PWR_SEL") (pin "2") (pinfunction "2_2") (pintype "bidirectional"))
      (node (ref "PWR_SEL") (pin "5") (pinfunction "5_5") (pintype "bidirectional"))
    )
    (net (code "94") (name "Net-(LED1-PadA)") (class "Default")
      (node (ref "LED1") (pin "A") (pinfunction "A_A") (pintype "passive"))
      (node (ref "R7") (pin "1") (pinfunction "1_1") (pintype "passive"))
    )
    (net (code "95") (name "Net-(LED2-PadA)") (class "Default")
      (node (ref "LED2") (pin "A") (pinfunction "A_A") (pintype "passive"))
      (node (ref "R6") (pin "1") (pinfunction "1_1") (pintype "passive"))
    )
    (net (code "96") (name "Net-(LED3-PadA)") (class "Default")
      (node (ref "LED3") (pin "A") (pinfunction "A_A") (pintype "passive"))
      (node (ref "R4") (pin "1") (pinfunction "1_1") (pintype "passive"))
    )
    (net (code "97") (name "Net-(PWR-PadA)") (class "Default")
      (node (ref "PWR") (pin "A") (pinfunction "A_A") (pintype "passive"))
      (node (ref "R11") (pin "1") (pinfunction "1_1") (pintype "passive"))
    )
    (net (code "98") (name "Net-(R8-Pad1)") (class "Default")
      (node (ref "R8") (pin "1") (pinfunction "1_1") (pintype "passive"))
      (node (ref "USB") (pin "A") (pinfunction "A_A") (pintype "passive"))
    )
    (net (code "99") (name "Net-(U2-ADJ)") (class "Default")
      (node (ref "R13") (pin "2") (pinfunction "2_2") (pintype "passive"))
      (node (ref "R14") (pin "2") (pinfunction "2_2") (pintype "passive"))
      (node (ref "U2") (pin "1") (pinfunction "ADJ_1") (pintype "input"))
    )
    (net (code "100") (name "Net-(U3-ADJ)") (class "Default")
      (node (ref "R15") (pin "2") (pinfunction "2_2") (pintype "passive"))
      (node (ref "R16") (pin "2") (pinfunction "2_2") (pintype "passive"))
      (node (ref "U3") (pin "1") (pinfunction "ADJ_1") (pintype "input"))
    )
  )
)
